# G853A.net
KiCad netlist of a schematic drawn in EAGLE
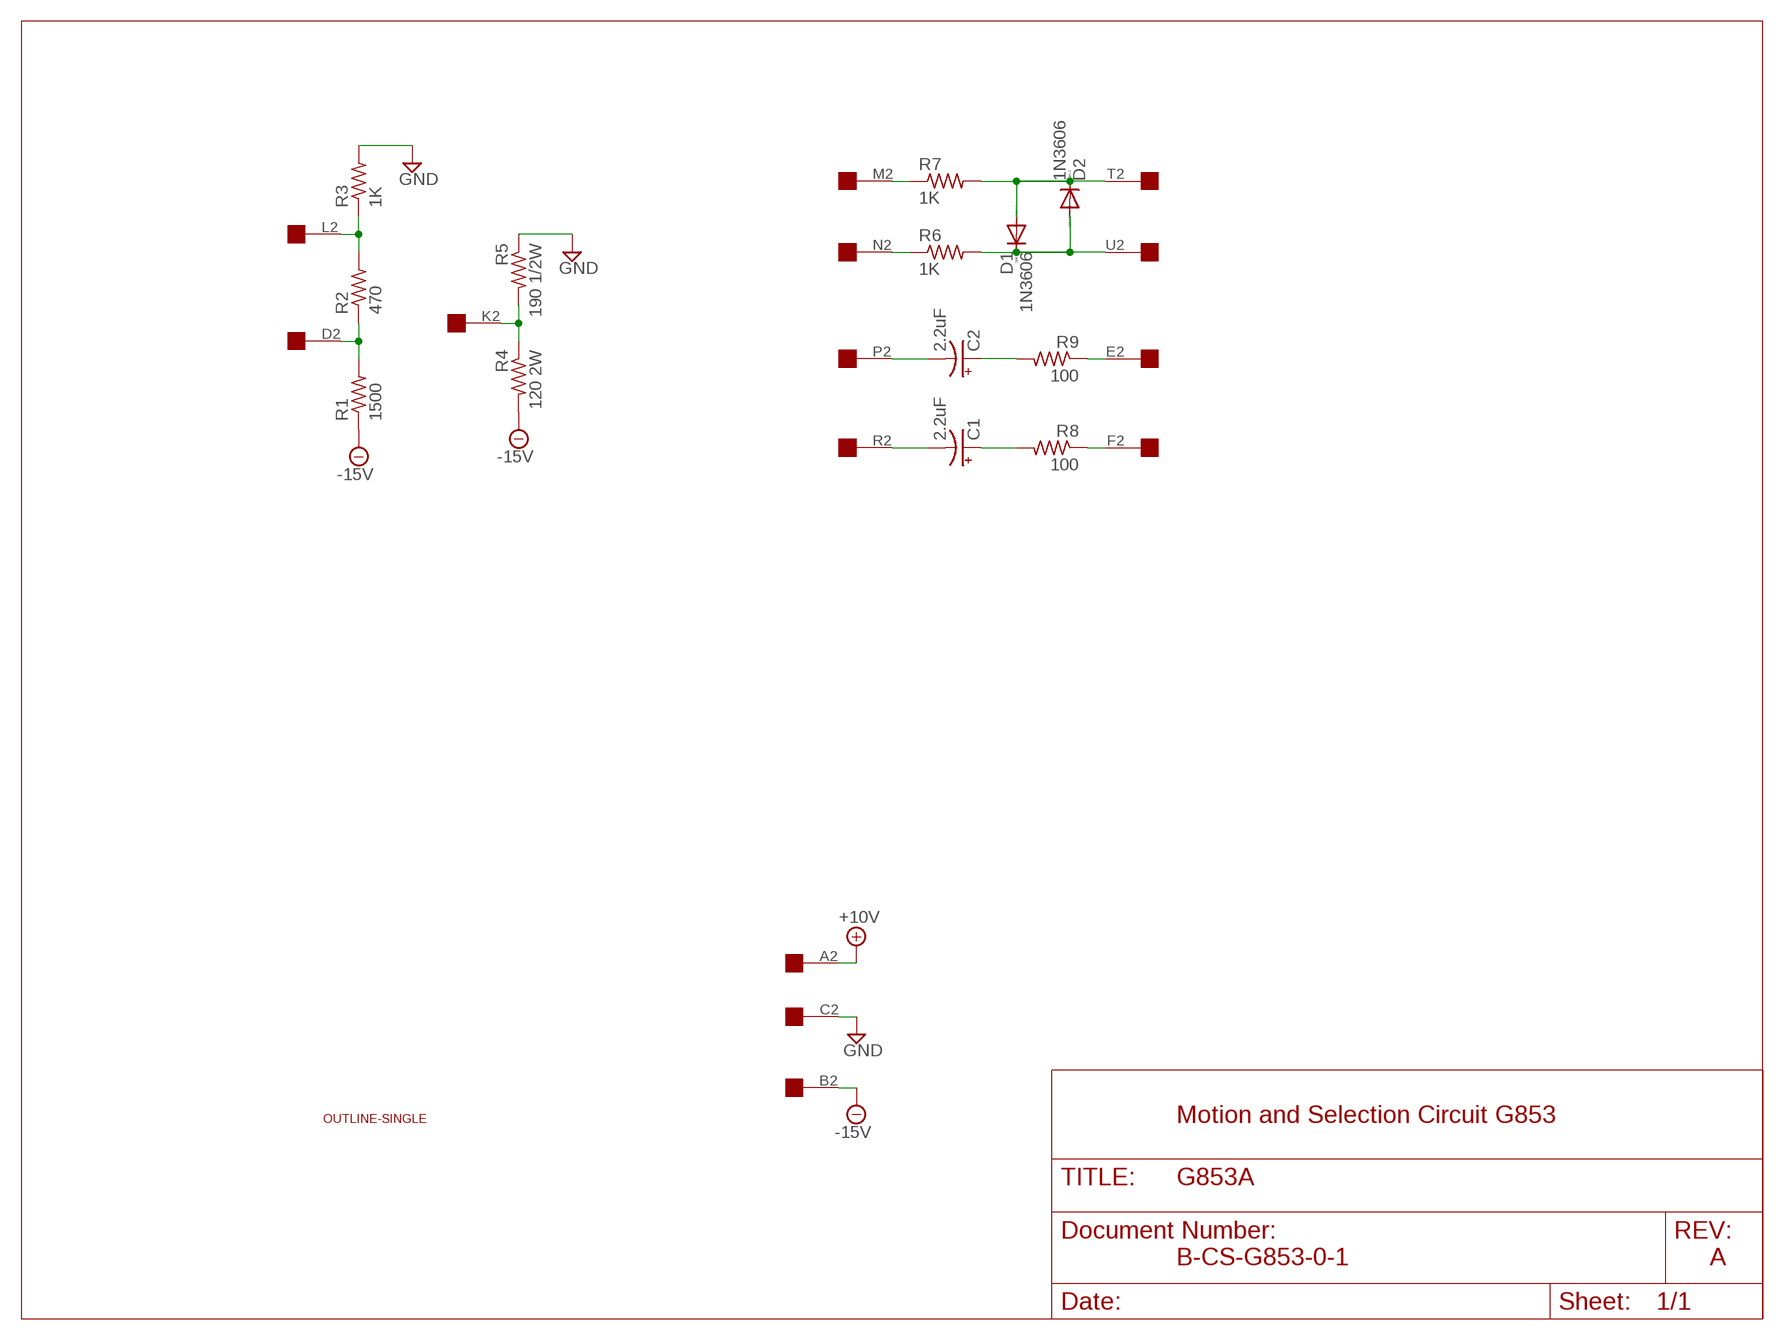
[diagram p0: schematic, sheet 1]

(export (version "E")
  (design (tool "Eeschema 10.0.6"))
  (components
    (comp (ref "C1")
      (value "2.2uF")
      (footprint "eagle-import:E15-5")
      (libsource (lib "eagle-import") (part "CPOL-USE15-5AXIAL"))
    )
    (comp (ref "C2")
      (value "2.2uF")
      (footprint "eagle-import:E15-5")
      (libsource (lib "eagle-import") (part "CPOL-USE15-5AXIAL"))
    )
    (comp (ref "D1")
      (value "1N3606")
      (footprint "eagle-import:DO35-10")
      (libsource (lib "eagle-import") (part "1N4148DO35-10"))
    )
    (comp (ref "D2")
      (value "1N3606")
      (footprint "eagle-import:DO35-10")
      (libsource (lib "eagle-import") (part "1N4148DO35-10"))
    )
    (comp (ref "R1")
      (value "1500")
      (footprint "eagle-import:0207_10")
      (libsource (lib "eagle-import") (part "R-US_0207/10"))
    )
    (comp (ref "R2")
      (value "470")
      (footprint "eagle-import:0207_10")
      (libsource (lib "eagle-import") (part "R-US_0207/10"))
    )
    (comp (ref "R3")
      (value "1K")
      (footprint "eagle-import:0207_10")
      (libsource (lib "eagle-import") (part "R-US_0207/10"))
    )
    (comp (ref "R4")
      (value "120 2W")
      (footprint "eagle-import:P0817_22")
      (libsource (lib "eagle-import") (part "R-US_0817/22"))
    )
    (comp (ref "R5")
      (value "190 1/2W")
      (footprint "eagle-import:0309_12")
      (libsource (lib "eagle-import") (part "R-US_0309/12"))
    )
    (comp (ref "R6")
      (value "1K")
      (footprint "eagle-import:0207_10")
      (libsource (lib "eagle-import") (part "R-US_0207/10"))
    )
    (comp (ref "R7")
      (value "1K")
      (footprint "eagle-import:0207_10")
      (libsource (lib "eagle-import") (part "R-US_0207/10"))
    )
    (comp (ref "R8")
      (value "100")
      (footprint "eagle-import:0207_10")
      (libsource (lib "eagle-import") (part "R-US_0207/10"))
    )
    (comp (ref "R9")
      (value "100")
      (footprint "eagle-import:0207_10")
      (libsource (lib "eagle-import") (part "R-US_0207/10"))
    )
    (comp (ref "U$1")
      (value "OUTLINE-SINGLE")
      (footprint "eagle-import:SINGLE")
      (libsource (lib "eagle-import") (part "OUTLINE-SINGLE"))
    )
    (comp (ref "U$2")
      (value "EDGE-1")
      (footprint "eagle-import:EDGE-CON1")
      (libsource (lib "eagle-import") (part "EDGE-1"))
    )
  )
  (nets
    (net (code "1") (name "+10V") (class "Default")
      (node (ref "U$2") (pin "A2") (pinfunction "1_A2") (pintype "bidirectional"))
    )
    (net (code "2") (name "-15V") (class "Default")
      (node (ref "R1") (pin "1") (pinfunction "1_1") (pintype "passive"))
      (node (ref "R4") (pin "2") (pinfunction "2_2") (pintype "passive"))
      (node (ref "U$2") (pin "B2") (pinfunction "1_B2") (pintype "bidirectional"))
    )
    (net (code "3") (name "GND") (class "Default")
      (node (ref "R3") (pin "2") (pinfunction "2_2") (pintype "passive"))
      (node (ref "R5") (pin "1") (pinfunction "1_1") (pintype "passive"))
      (node (ref "U$2") (pin "C2") (pinfunction "1_C2") (pintype "bidirectional"))
    )
    (net (code "4") (name "Net-(C1-Pad+)") (class "Default")
      (node (ref "C1") (pin "+") (pinfunction "+_+") (pintype "passive"))
      (node (ref "R8") (pin "2") (pinfunction "2_2") (pintype "passive"))
    )
    (net (code "5") (name "Net-(C2-Pad+)") (class "Default")
      (node (ref "C2") (pin "+") (pinfunction "+_+") (pintype "passive"))
      (node (ref "R9") (pin "2") (pinfunction "2_2") (pintype "passive"))
    )
    (net (code "6") (name "Net-(U$2D-1)") (class "Default")
      (node (ref "R1") (pin "2") (pinfunction "2_2") (pintype "passive"))
      (node (ref "R2") (pin "1") (pinfunction "1_1") (pintype "passive"))
      (node (ref "U$2") (pin "D2") (pinfunction "1_D2") (pintype "bidirectional"))
    )
    (net (code "7") (name "Net-(U$2E-1)") (class "Default")
      (node (ref "R9") (pin "1") (pinfunction "1_1") (pintype "passive"))
      (node (ref "U$2") (pin "E2") (pinfunction "1_E2") (pintype "bidirectional"))
    )
    (net (code "8") (name "Net-(U$2F-1)") (class "Default")
      (node (ref "R8") (pin "1") (pinfunction "1_1") (pintype "passive"))
      (node (ref "U$2") (pin "F2") (pinfunction "1_F2") (pintype "bidirectional"))
    )
    (net (code "9") (name "Net-(U$2I-1)") (class "Default")
      (node (ref "R4") (pin "1") (pinfunction "1_1") (pintype "passive"))
      (node (ref "R5") (pin "2") (pinfunction "2_2") (pintype "passive"))
      (node (ref "U$2") (pin "K2") (pinfunction "1_K2") (pintype "bidirectional"))
    )
    (net (code "10") (name "Net-(U$2J-1)") (class "Default")
      (node (ref "R2") (pin "2") (pinfunction "2_2") (pintype "passive"))
      (node (ref "R3") (pin "1") (pinfunction "1_1") (pintype "passive"))
      (node (ref "U$2") (pin "L2") (pinfunction "1_L2") (pintype "bidirectional"))
    )
    (net (code "11") (name "Net-(U$2K-1)") (class "Default")
      (node (ref "R7") (pin "1") (pinfunction "1_1") (pintype "passive"))
      (node (ref "U$2") (pin "M2") (pinfunction "1_M2") (pintype "bidirectional"))
    )
    (net (code "12") (name "Net-(U$2L-1)") (class "Default")
      (node (ref "R6") (pin "1") (pinfunction "1_1") (pintype "passive"))
      (node (ref "U$2") (pin "N2") (pinfunction "1_N2") (pintype "bidirectional"))
    )
    (net (code "13") (name "Net-(U$2M-1)") (class "Default")
      (node (ref "C2") (pin "-") (pinfunction "-_-") (pintype "passive"))
      (node (ref "U$2") (pin "P2") (pinfunction "1_P2") (pintype "bidirectional"))
    )
    (net (code "14") (name "Net-(U$2N-1)") (class "Default")
      (node (ref "C1") (pin "-") (pinfunction "-_-") (pintype "passive"))
      (node (ref "U$2") (pin "R2") (pinfunction "1_R2") (pintype "bidirectional"))
    )
    (net (code "15") (name "Net-(U$2P-1)") (class "Default")
      (node (ref "D1") (pin "A") (pinfunction "A_A") (pintype "passive"))
      (node (ref "D2") (pin "C") (pinfunction "C_C") (pintype "passive"))
      (node (ref "R7") (pin "2") (pinfunction "2_2") (pintype "passive"))
      (node (ref "U$2") (pin "T2") (pinfunction "1_T2") (pintype "bidirectional"))
    )
    (net (code "16") (name "Net-(U$2Q-1)") (class "Default")
      (node (ref "D1") (pin "C") (pinfunction "C_C") (pintype "passive"))
      (node (ref "D2") (pin "A") (pinfunction "A_A") (pintype "passive"))
      (node (ref "R6") (pin "2") (pinfunction "2_2") (pintype "passive"))
      (node (ref "U$2") (pin "U2") (pinfunction "1_U2") (pintype "bidirectional"))
    )
  )
)
